# UART_Interface.net
KiCad netlist of a schematic drawn in Altium Designer
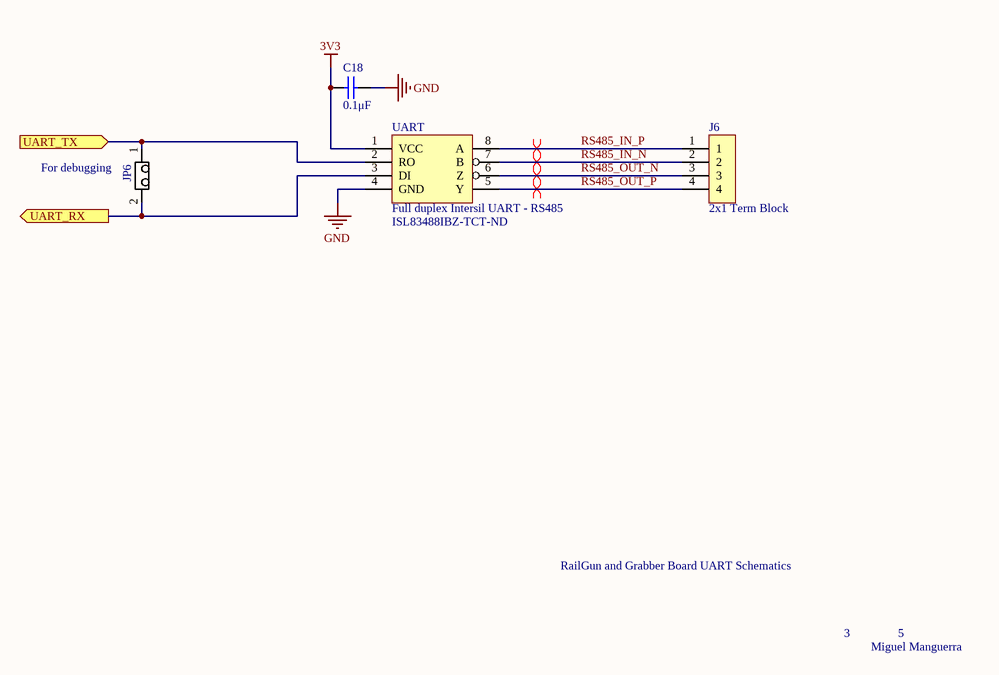
[diagram p0: UART Interface.SchDoc]

(export (version "E")
  (design (tool "Eeschema 10.0.6"))
  (components
    (comp (ref "C18")
      (value "0.1μF")
      (footprint "CAPC1608N(0603\")")
      (description "Capacitor, Ceramic, 100V, +/- 10%, 0603 SMD, X7R")
      (fields
        (field (name "MFG") "TDK")
        (field (name "PUBLISHER") "AUVic")
        (field (name "CREATED BY") "Ashwin Sira")
      )
      (libsource (lib "AUVic_Integrated_Library_Capacitors") (part "0.1uF 100V 0603 SMD, Ceramic"))
    )
    (comp (ref "J6")
      (value "2x1 Term Block")
      (footprint "4X1 Terminal Block")
      (fields (field (name "MADE BY") "Andy Bates"))
      (libsource (lib "AUVic_Integrated_Library_Connectors") (part "4x1 Terminal Block"))
    )
    (comp (ref "JP6")
      (value "1X2 Pin Head")
      (footprint "2X1 Males Header")
      (fields (field (name "MADE BY") "Andy Bates"))
      (libsource (lib "AUVic_Schematic_Library_Connectors") (part "1x2 Male Header"))
    )
    (comp (ref "UART")
      (value "Full duplex Intersil UART - RS485")
      (footprint "SOIC-SN8_M")
      (fields
        (field (name "SUPPLIER PART NUMBER 1") "ISL83488IBZ-TCT-ND")
        (field (name "MADE BY") "Andy Bates")
      )
      (libsource (lib "AUVic_Integrated_Library_Interface") (part "Full duplex Intersil UART - RS485"))
    )
  )
  (nets
    (net (code "1") (name "/RS485_IN_N") (class "Default")
      (node (ref "J6") (pin "2") (pinfunction "2_2") (pintype "passive"))
      (node (ref "UART") (pin "7") (pinfunction "B_7") (pintype "passive"))
    )
    (net (code "2") (name "/RS485_IN_P") (class "Default")
      (node (ref "J6") (pin "1") (pinfunction "1_1") (pintype "passive"))
      (node (ref "UART") (pin "8") (pinfunction "A_8") (pintype "passive"))
    )
    (net (code "3") (name "/RS485_OUT_N") (class "Default")
      (node (ref "J6") (pin "3") (pinfunction "3_3") (pintype "passive"))
      (node (ref "UART") (pin "6") (pinfunction "Z_6") (pintype "passive"))
    )
    (net (code "4") (name "/RS485_OUT_P") (class "Default")
      (node (ref "J6") (pin "4") (pinfunction "4_4") (pintype "passive"))
      (node (ref "UART") (pin "5") (pinfunction "Y_5") (pintype "passive"))
    )
    (net (code "5") (name "/UART_RX") (class "Default")
      (node (ref "JP6") (pin "2") (pinfunction "2_2") (pintype "passive"))
      (node (ref "UART") (pin "3") (pinfunction "DI_3") (pintype "passive"))
    )
    (net (code "6") (name "/UART_TX") (class "Default")
      (node (ref "JP6") (pin "1") (pinfunction "1_1") (pintype "passive"))
      (node (ref "UART") (pin "2") (pinfunction "RO_2") (pintype "passive"))
    )
    (net (code "7") (name "3V3") (class "Default")
      (node (ref "C18") (pin "2") (pinfunction "Cathode_2") (pintype "passive"))
      (node (ref "UART") (pin "1") (pinfunction "VCC_1") (pintype "passive"))
    )
    (net (code "8") (name "GND") (class "Default")
      (node (ref "C18") (pin "1") (pinfunction "Anode_1") (pintype "passive"))
      (node (ref "UART") (pin "4") (pinfunction "GND_4") (pintype "passive"))
    )
  )
)
